# rel-eeprom-prog.net
KiCad netlist of a schematic drawn in EAGLE
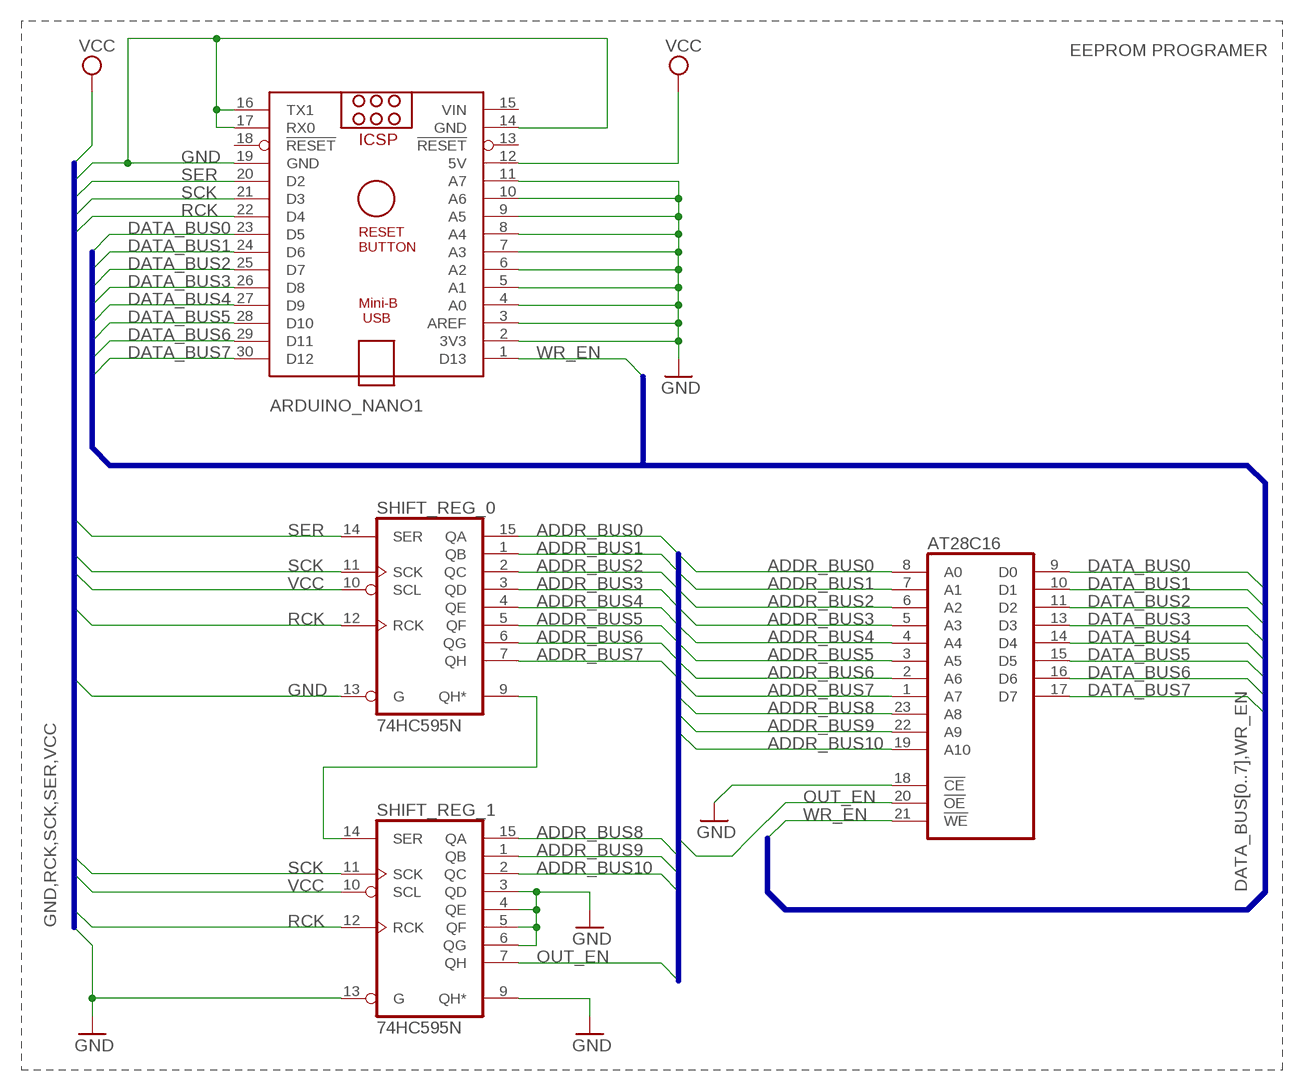
[diagram p0: schematic, sheet 1]

(export (version "E")
  (design (tool "Eeschema 10.0.6"))
  (components
    (comp (ref "ARDUINO_NANO1")
      (value "ARDUINO_NANO")
      (footprint "eagle-import:ARDUINO_NANO")
      (libsource (lib "eagle-import") (part "ARDUINO_NANO"))
    )
    (comp (ref "AT28C16")
      (value "2816")
      (footprint "eagle-import:DIL24")
      (libsource (lib "eagle-import") (part "2816"))
    )
    (comp (ref "SHIFT_REG_0")
      (value "74HC595N")
      (footprint "eagle-import:DIL16")
      (libsource (lib "eagle-import") (part "74595NHC"))
    )
    (comp (ref "SHIFT_REG_1")
      (value "74HC595N")
      (footprint "eagle-import:DIL16")
      (libsource (lib "eagle-import") (part "74595NHC"))
    )
  )
  (nets
    (net (code "1") (name "/ADDR_BUS0") (class "Default")
      (node (ref "AT28C16") (pin "8") (pinfunction "A0_8") (pintype "input"))
      (node (ref "SHIFT_REG_0") (pin "15") (pinfunction "QA_15") (pintype "tri_state"))
    )
    (net (code "2") (name "/ADDR_BUS1") (class "Default")
      (node (ref "AT28C16") (pin "7") (pinfunction "A1_7") (pintype "input"))
      (node (ref "SHIFT_REG_0") (pin "1") (pinfunction "QB_1") (pintype "tri_state"))
    )
    (net (code "3") (name "/ADDR_BUS2") (class "Default")
      (node (ref "AT28C16") (pin "6") (pinfunction "A2_6") (pintype "input"))
      (node (ref "SHIFT_REG_0") (pin "2") (pinfunction "QC_2") (pintype "tri_state"))
    )
    (net (code "4") (name "/ADDR_BUS3") (class "Default")
      (node (ref "AT28C16") (pin "5") (pinfunction "A3_5") (pintype "input"))
      (node (ref "SHIFT_REG_0") (pin "3") (pinfunction "QD_3") (pintype "tri_state"))
    )
    (net (code "5") (name "/ADDR_BUS4") (class "Default")
      (node (ref "AT28C16") (pin "4") (pinfunction "A4_4") (pintype "input"))
      (node (ref "SHIFT_REG_0") (pin "4") (pinfunction "QE_4") (pintype "tri_state"))
    )
    (net (code "6") (name "/ADDR_BUS5") (class "Default")
      (node (ref "AT28C16") (pin "3") (pinfunction "A5_3") (pintype "input"))
      (node (ref "SHIFT_REG_0") (pin "5") (pinfunction "QF_5") (pintype "tri_state"))
    )
    (net (code "7") (name "/ADDR_BUS6") (class "Default")
      (node (ref "AT28C16") (pin "2") (pinfunction "A6_2") (pintype "input"))
      (node (ref "SHIFT_REG_0") (pin "6") (pinfunction "QG_6") (pintype "tri_state"))
    )
    (net (code "8") (name "/ADDR_BUS7") (class "Default")
      (node (ref "AT28C16") (pin "1") (pinfunction "A7_1") (pintype "input"))
      (node (ref "SHIFT_REG_0") (pin "7") (pinfunction "QH_7") (pintype "tri_state"))
    )
    (net (code "9") (name "/ADDR_BUS8") (class "Default")
      (node (ref "AT28C16") (pin "23") (pinfunction "A8_23") (pintype "input"))
      (node (ref "SHIFT_REG_1") (pin "15") (pinfunction "QA_15") (pintype "tri_state"))
    )
    (net (code "10") (name "/ADDR_BUS9") (class "Default")
      (node (ref "AT28C16") (pin "22") (pinfunction "A9_22") (pintype "input"))
      (node (ref "SHIFT_REG_1") (pin "1") (pinfunction "QB_1") (pintype "tri_state"))
    )
    (net (code "11") (name "/ADDR_BUS10") (class "Default")
      (node (ref "AT28C16") (pin "19") (pinfunction "A10_19") (pintype "input"))
      (node (ref "SHIFT_REG_1") (pin "2") (pinfunction "QC_2") (pintype "tri_state"))
    )
    (net (code "12") (name "/DATA_BUS0") (class "Default")
      (node (ref "ARDUINO_NANO1") (pin "23") (pinfunction "D5_23") (pintype "bidirectional"))
      (node (ref "AT28C16") (pin "9") (pinfunction "D0_9") (pintype "bidirectional"))
    )
    (net (code "13") (name "/DATA_BUS1") (class "Default")
      (node (ref "ARDUINO_NANO1") (pin "24") (pinfunction "D6_24") (pintype "bidirectional"))
      (node (ref "AT28C16") (pin "10") (pinfunction "D1_10") (pintype "bidirectional"))
    )
    (net (code "14") (name "/DATA_BUS2") (class "Default")
      (node (ref "ARDUINO_NANO1") (pin "25") (pinfunction "D7_25") (pintype "bidirectional"))
      (node (ref "AT28C16") (pin "11") (pinfunction "D2_11") (pintype "bidirectional"))
    )
    (net (code "15") (name "/DATA_BUS3") (class "Default")
      (node (ref "ARDUINO_NANO1") (pin "26") (pinfunction "D8_26") (pintype "bidirectional"))
      (node (ref "AT28C16") (pin "13") (pinfunction "D3_13") (pintype "bidirectional"))
    )
    (net (code "16") (name "/DATA_BUS4") (class "Default")
      (node (ref "ARDUINO_NANO1") (pin "27") (pinfunction "D9_27") (pintype "bidirectional"))
      (node (ref "AT28C16") (pin "14") (pinfunction "D4_14") (pintype "bidirectional"))
    )
    (net (code "17") (name "/DATA_BUS5") (class "Default")
      (node (ref "ARDUINO_NANO1") (pin "28") (pinfunction "D10_28") (pintype "bidirectional"))
      (node (ref "AT28C16") (pin "15") (pinfunction "D5_15") (pintype "bidirectional"))
    )
    (net (code "18") (name "/DATA_BUS6") (class "Default")
      (node (ref "ARDUINO_NANO1") (pin "29") (pinfunction "D11_29") (pintype "bidirectional"))
      (node (ref "AT28C16") (pin "16") (pinfunction "D6_16") (pintype "bidirectional"))
    )
    (net (code "19") (name "/DATA_BUS7") (class "Default")
      (node (ref "ARDUINO_NANO1") (pin "30") (pinfunction "D12_30") (pintype "bidirectional"))
      (node (ref "AT28C16") (pin "17") (pinfunction "D7_17") (pintype "bidirectional"))
    )
    (net (code "20") (name "/OUT_EN") (class "Default")
      (node (ref "AT28C16") (pin "20") (pinfunction "~{OE}_20") (pintype "input"))
      (node (ref "SHIFT_REG_1") (pin "7") (pinfunction "QH_7") (pintype "tri_state"))
    )
    (net (code "21") (name "/RCK") (class "Default")
      (node (ref "ARDUINO_NANO1") (pin "22") (pinfunction "D4_22") (pintype "bidirectional"))
      (node (ref "SHIFT_REG_0") (pin "12") (pinfunction "RCK_12") (pintype "input"))
      (node (ref "SHIFT_REG_1") (pin "12") (pinfunction "RCK_12") (pintype "input"))
    )
    (net (code "22") (name "/SCK") (class "Default")
      (node (ref "ARDUINO_NANO1") (pin "21") (pinfunction "D3_21") (pintype "bidirectional"))
      (node (ref "SHIFT_REG_0") (pin "11") (pinfunction "SCK_11") (pintype "input"))
      (node (ref "SHIFT_REG_1") (pin "11") (pinfunction "SCK_11") (pintype "input"))
    )
    (net (code "23") (name "/SER") (class "Default")
      (node (ref "ARDUINO_NANO1") (pin "20") (pinfunction "D2_20") (pintype "bidirectional"))
      (node (ref "SHIFT_REG_0") (pin "14") (pinfunction "SER_14") (pintype "input"))
    )
    (net (code "24") (name "/VIN") (class "Default")
      (node (ref "ARDUINO_NANO1") (pin "15") (pinfunction "VIN_15") (pintype "power_in"))
    )
    (net (code "25") (name "/WR_EN") (class "Default")
      (node (ref "ARDUINO_NANO1") (pin "1") (pinfunction "D13_1") (pintype "bidirectional"))
      (node (ref "AT28C16") (pin "21") (pinfunction "~{WE}_21") (pintype "input"))
    )
    (net (code "28") (name "GND") (class "Default")
      (node (ref "ARDUINO_NANO1") (pin "10") (pinfunction "A6_10") (pintype "bidirectional"))
      (node (ref "ARDUINO_NANO1") (pin "11") (pinfunction "A7_11") (pintype "bidirectional"))
      (node (ref "ARDUINO_NANO1") (pin "14") (pinfunction "GND_14") (pintype "power_in"))
      (node (ref "ARDUINO_NANO1") (pin "16") (pinfunction "TX1_16") (pintype "bidirectional"))
      (node (ref "ARDUINO_NANO1") (pin "17") (pinfunction "RX0_17") (pintype "bidirectional"))
      (node (ref "ARDUINO_NANO1") (pin "19") (pinfunction "GND_19") (pintype "power_in"))
      (node (ref "ARDUINO_NANO1") (pin "2") (pinfunction "3V3_2") (pintype "output"))
      (node (ref "ARDUINO_NANO1") (pin "3") (pinfunction "AREF_3") (pintype "input"))
      (node (ref "ARDUINO_NANO1") (pin "4") (pinfunction "A0_4") (pintype "bidirectional"))
      (node (ref "ARDUINO_NANO1") (pin "5") (pinfunction "A1_5") (pintype "bidirectional"))
      (node (ref "ARDUINO_NANO1") (pin "6") (pinfunction "A2_6") (pintype "bidirectional"))
      (node (ref "ARDUINO_NANO1") (pin "7") (pinfunction "A3_7") (pintype "bidirectional"))
      (node (ref "ARDUINO_NANO1") (pin "8") (pinfunction "A4_8") (pintype "bidirectional"))
      (node (ref "ARDUINO_NANO1") (pin "9") (pinfunction "A5_9") (pintype "bidirectional"))
      (node (ref "AT28C16") (pin "18") (pinfunction "~{CE}_18") (pintype "input"))
      (node (ref "SHIFT_REG_0") (pin "13") (pinfunction "G_13") (pintype "input"))
      (node (ref "SHIFT_REG_1") (pin "13") (pinfunction "G_13") (pintype "input"))
      (node (ref "SHIFT_REG_1") (pin "3") (pinfunction "QD_3") (pintype "tri_state"))
      (node (ref "SHIFT_REG_1") (pin "4") (pinfunction "QE_4") (pintype "tri_state"))
      (node (ref "SHIFT_REG_1") (pin "5") (pinfunction "QF_5") (pintype "tri_state"))
      (node (ref "SHIFT_REG_1") (pin "6") (pinfunction "QG_6") (pintype "tri_state"))
      (node (ref "SHIFT_REG_1") (pin "9") (pinfunction "QH*_9") (pintype "tri_state"))
    )
    (net (code "29") (name "Net-(SHIFT_REG_0A-QH*)") (class "Default")
      (node (ref "SHIFT_REG_0") (pin "9") (pinfunction "QH*_9") (pintype "tri_state"))
      (node (ref "SHIFT_REG_1") (pin "14") (pinfunction "SER_14") (pintype "input"))
    )
    (net (code "30") (name "VCC") (class "Default")
      (node (ref "ARDUINO_NANO1") (pin "12") (pinfunction "5V_12") (pintype "power_in"))
      (node (ref "SHIFT_REG_0") (pin "10") (pinfunction "SCL_10") (pintype "input"))
      (node (ref "SHIFT_REG_1") (pin "10") (pinfunction "SCL_10") (pintype "input"))
    )
    (net (code "31") (name "unconnected-(ARDUINO_NANO1-~{RESET}-Pad13)") (class "Default")
      (node (ref "ARDUINO_NANO1") (pin "13") (pinfunction "~{RESET}_13") (pintype "input"))
    )
    (net (code "32") (name "unconnected-(ARDUINO_NANO1-~{RESET}-Pad18)") (class "Default")
      (node (ref "ARDUINO_NANO1") (pin "18") (pinfunction "~{RESET}_18") (pintype "input"))
    )
  )
)
